# board.net
KiCad netlist of a schematic drawn in EAGLE
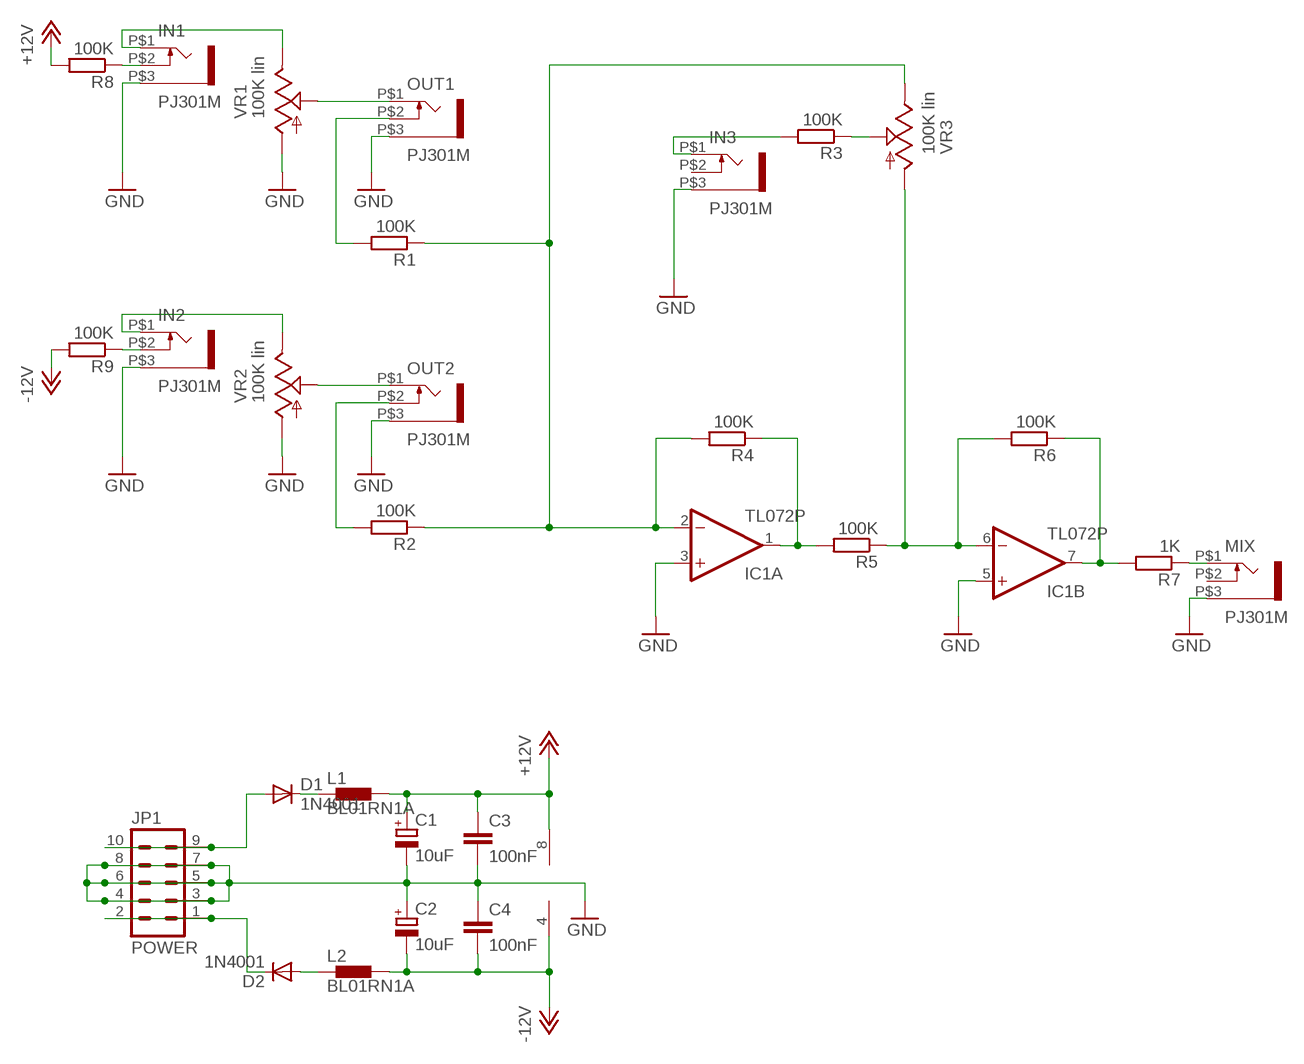
[diagram p0: schematic, sheet 1]

(export (version "E")
  (design (tool "Eeschema 10.0.6"))
  (components
    (comp (ref "C1")
      (value "10uF")
      (footprint "eagle-import:E2,5-6E")
      (fields (field (name "MF") "NICHICON") (field (name "MPN") "UVR2A100MED1TD"))
      (libsource (lib "eagle-import") (part "CPOL-EUE2,5-6E"))
    )
    (comp (ref "C2")
      (value "10uF")
      (footprint "eagle-import:E2,5-6E")
      (fields (field (name "MF") "NICHICON") (field (name "MPN") "UVR2A100MED1TD"))
      (libsource (lib "eagle-import") (part "CPOL-EUE2,5-6E"))
    )
    (comp (ref "C3")
      (value "100nF")
      (footprint "eagle-import:C025-024X044")
      (fields (field (name "MF") "MULTICOMP") (field (name "MPN") "MC0805Y104M500A2.54MM"))
      (libsource (lib "eagle-import") (part "C-EU025-024X044"))
    )
    (comp (ref "C4")
      (value "100nF")
      (footprint "eagle-import:C025-024X044")
      (fields (field (name "MF") "MULTICOMP") (field (name "MPN") "MC0805Y104M500A2.54MM"))
      (libsource (lib "eagle-import") (part "C-EU025-024X044"))
    )
    (comp (ref "D1")
      (value "1N4001")
      (footprint "eagle-import:DO41-10")
      (fields (field (name "MF") "VISHAY") (field (name "MPN") "1N4001-E3/54"))
      (libsource (lib "eagle-import") (part "1N4004"))
    )
    (comp (ref "D2")
      (value "1N4001")
      (footprint "eagle-import:DO41-10")
      (fields (field (name "MF") "VISHAY") (field (name "MPN") "1N4001-E3/54"))
      (libsource (lib "eagle-import") (part "1N4004"))
    )
    (comp (ref "IC1")
      (value "TL072P")
      (footprint "eagle-import:DIL08")
      (fields
        (field (name "MF") "TEXAS INSTRUMENTS")
        (field (name "MPN") "TL072IP")
        (field (name "OC_FARNELL") "3117794")
      )
      (libsource (lib "eagle-import") (part "TL072P"))
    )
    (comp (ref "IN1")
      (value "PJ301M")
      (footprint "eagle-import:WQP-PJ301M-12_JACK")
      (libsource (lib "eagle-import") (part "WQP-PJ301M-12_JACK"))
    )
    (comp (ref "IN2")
      (value "PJ301M")
      (footprint "eagle-import:WQP-PJ301M-12_JACK")
      (libsource (lib "eagle-import") (part "WQP-PJ301M-12_JACK"))
    )
    (comp (ref "IN3")
      (value "PJ301M")
      (footprint "eagle-import:WQP-PJ301M-12_JACK")
      (libsource (lib "eagle-import") (part "WQP-PJ301M-12_JACK"))
    )
    (comp (ref "JP1")
      (value "POWER")
      (footprint "eagle-import:EURO_PWR_HEADER_FAT")
      (fields (field (name "MF") "MULTICOMP PRO") (field (name "MPN") "2213S-10G"))
      (libsource (lib "eagle-import") (part "EURO_POWER_HEADERFAT_PADS"))
    )
    (comp (ref "L1")
      (value "BL01RN1A")
      (footprint "eagle-import:BL01RN1A")
      (fields (field (name "MF") "MURATA") (field (name "MPN") "BL01RN1A1D2B"))
      (libsource (lib "eagle-import") (part "BL01RN1A"))
    )
    (comp (ref "L2")
      (value "BL01RN1A")
      (footprint "eagle-import:BL01RN1A")
      (fields (field (name "MF") "MURATA") (field (name "MPN") "BL01RN1A1D2B"))
      (libsource (lib "eagle-import") (part "BL01RN1A"))
    )
    (comp (ref "MIX")
      (value "PJ301M")
      (footprint "eagle-import:WQP-PJ301M-12_JACK")
      (libsource (lib "eagle-import") (part "WQP-PJ301M-12_JACK"))
    )
    (comp (ref "OUT1")
      (value "PJ301M")
      (footprint "eagle-import:WQP-PJ301M-12_JACK")
      (libsource (lib "eagle-import") (part "WQP-PJ301M-12_JACK"))
    )
    (comp (ref "OUT2")
      (value "PJ301M")
      (footprint "eagle-import:WQP-PJ301M-12_JACK")
      (libsource (lib "eagle-import") (part "WQP-PJ301M-12_JACK"))
    )
    (comp (ref "R1")
      (value "100K")
      (footprint "eagle-import:0204_5")
      (fields (field (name "MF") "TE CONNECTIVITY") (field (name "MPN") "LR0204F100K"))
      (libsource (lib "eagle-import") (part "R-EU_0204/5"))
    )
    (comp (ref "R2")
      (value "100K")
      (footprint "eagle-import:0204_5")
      (fields (field (name "MF") "TE CONNECTIVITY") (field (name "MPN") "LR0204F100K"))
      (libsource (lib "eagle-import") (part "R-EU_0204/5"))
    )
    (comp (ref "R3")
      (value "100K")
      (footprint "eagle-import:0204_5")
      (fields (field (name "MF") "TE CONNECTIVITY") (field (name "MPN") "LR0204F100K"))
      (libsource (lib "eagle-import") (part "R-EU_0204/5"))
    )
    (comp (ref "R4")
      (value "100K")
      (footprint "eagle-import:0204_5")
      (fields (field (name "MF") "TE CONNECTIVITY") (field (name "MPN") "LR0204F100K"))
      (libsource (lib "eagle-import") (part "R-EU_0204/5"))
    )
    (comp (ref "R5")
      (value "100K")
      (footprint "eagle-import:0204_5")
      (fields (field (name "MF") "TE CONNECTIVITY") (field (name "MPN") "LR0204F100K"))
      (libsource (lib "eagle-import") (part "R-EU_0204/5"))
    )
    (comp (ref "R6")
      (value "100K")
      (footprint "eagle-import:0204_5")
      (fields (field (name "MF") "TE CONNECTIVITY") (field (name "MPN") "LR0204F100K"))
      (libsource (lib "eagle-import") (part "R-EU_0204/5"))
    )
    (comp (ref "R7")
      (value "1K")
      (footprint "eagle-import:0204_5")
      (fields (field (name "MF") "TE CONNECTIVITY") (field (name "MPN") "LR0204F1K0"))
      (libsource (lib "eagle-import") (part "R-EU_0204/5"))
    )
    (comp (ref "R8")
      (value "100K")
      (footprint "eagle-import:0204_5")
      (fields (field (name "MF") "TE CONNECTIVITY") (field (name "MPN") "LR0204F100K"))
      (libsource (lib "eagle-import") (part "R-EU_0204/5"))
    )
    (comp (ref "R9")
      (value "100K")
      (footprint "eagle-import:0204_5")
      (fields (field (name "MF") "TE CONNECTIVITY") (field (name "MPN") "LR0204F100K"))
      (libsource (lib "eagle-import") (part "R-EU_0204/5"))
    )
    (comp (ref "VR1")
      (value "100K lin")
      (footprint "eagle-import:9MM_SNAP-IN_POT")
      (libsource (lib "eagle-import") (part "9MM_SNAP-IN_POT_"))
    )
    (comp (ref "VR2")
      (value "100K lin")
      (footprint "eagle-import:9MM_SNAP-IN_POT")
      (libsource (lib "eagle-import") (part "9MM_SNAP-IN_POT_"))
    )
    (comp (ref "VR3")
      (value "100K lin")
      (footprint "eagle-import:9MM_SNAP-IN_POT")
      (libsource (lib "eagle-import") (part "9MM_SNAP-IN_POT_"))
    )
  )
  (nets
    (net (code "1") (name "+12V") (class "Default")
      (node (ref "C1") (pin "+") (pinfunction "+_+") (pintype "passive"))
      (node (ref "C3") (pin "1") (pinfunction "1_1") (pintype "passive"))
      (node (ref "IC1") (pin "8") (pinfunction "V+_8") (pintype "power_in"))
      (node (ref "L1") (pin "2") (pinfunction "2_2") (pintype "passive"))
      (node (ref "R8") (pin "2") (pinfunction "2_2") (pintype "passive"))
    )
    (net (code "2") (name "-12V") (class "Default")
      (node (ref "C2") (pin "-") (pinfunction "-_-") (pintype "passive"))
      (node (ref "C4") (pin "2") (pinfunction "2_2") (pintype "passive"))
      (node (ref "IC1") (pin "4") (pinfunction "V-_4") (pintype "power_in"))
      (node (ref "L2") (pin "2") (pinfunction "2_2") (pintype "passive"))
      (node (ref "R9") (pin "2") (pinfunction "2_2") (pintype "passive"))
    )
    (net (code "3") (name "GND") (class "Default")
      (node (ref "C1") (pin "-") (pinfunction "-_-") (pintype "passive"))
      (node (ref "C2") (pin "+") (pinfunction "+_+") (pintype "passive"))
      (node (ref "C3") (pin "2") (pinfunction "2_2") (pintype "passive"))
      (node (ref "C4") (pin "1") (pinfunction "1_1") (pintype "passive"))
      (node (ref "IC1") (pin "3") (pinfunction "+IN_3") (pintype "input"))
      (node (ref "IC1") (pin "5") (pinfunction "+IN_5") (pintype "input"))
      (node (ref "IN1") (pin "P$3") (pinfunction "1_P$3") (pintype "passive"))
      (node (ref "IN2") (pin "P$3") (pinfunction "1_P$3") (pintype "passive"))
      (node (ref "IN3") (pin "P$3") (pinfunction "1_P$3") (pintype "passive"))
      (node (ref "JP1") (pin "3") (pinfunction "3_3") (pintype "passive"))
      (node (ref "JP1") (pin "4") (pinfunction "4_4") (pintype "passive"))
      (node (ref "JP1") (pin "5") (pinfunction "5_5") (pintype "passive"))
      (node (ref "JP1") (pin "6") (pinfunction "6_6") (pintype "passive"))
      (node (ref "JP1") (pin "7") (pinfunction "7_7") (pintype "passive"))
      (node (ref "JP1") (pin "8") (pinfunction "8_8") (pintype "passive"))
      (node (ref "MIX") (pin "P$3") (pinfunction "1_P$3") (pintype "passive"))
      (node (ref "OUT1") (pin "P$3") (pinfunction "1_P$3") (pintype "passive"))
      (node (ref "OUT2") (pin "P$3") (pinfunction "1_P$3") (pintype "passive"))
      (node (ref "VR1") (pin "1") (pinfunction "A_1") (pintype "passive"))
      (node (ref "VR2") (pin "1") (pinfunction "A_1") (pintype "passive"))
    )
    (net (code "4") (name "Net-(D1-PadA)") (class "Default")
      (node (ref "D1") (pin "A") (pinfunction "A_A") (pintype "passive"))
      (node (ref "JP1") (pin "10") (pinfunction "10_10") (pintype "passive"))
      (node (ref "JP1") (pin "9") (pinfunction "9_9") (pintype "passive"))
    )
    (net (code "5") (name "Net-(D1-PadC)") (class "Default")
      (node (ref "D1") (pin "C") (pinfunction "C_C") (pintype "passive"))
      (node (ref "L1") (pin "1") (pinfunction "1_1") (pintype "passive"))
    )
    (net (code "6") (name "Net-(D2-PadA)") (class "Default")
      (node (ref "D2") (pin "A") (pinfunction "A_A") (pintype "passive"))
      (node (ref "L2") (pin "1") (pinfunction "1_1") (pintype "passive"))
    )
    (net (code "7") (name "Net-(D2-PadC)") (class "Default")
      (node (ref "D2") (pin "C") (pinfunction "C_C") (pintype "passive"))
      (node (ref "JP1") (pin "1") (pinfunction "1_1") (pintype "passive"))
      (node (ref "JP1") (pin "2") (pinfunction "2_2") (pintype "passive"))
    )
    (net (code "8") (name "Net-(IC1A--IN)") (class "Default")
      (node (ref "IC1") (pin "2") (pinfunction "-IN_2") (pintype "input"))
      (node (ref "R1") (pin "1") (pinfunction "1_1") (pintype "passive"))
      (node (ref "R2") (pin "1") (pinfunction "1_1") (pintype "passive"))
      (node (ref "R4") (pin "2") (pinfunction "2_2") (pintype "passive"))
      (node (ref "VR3") (pin "3") (pinfunction "E_3") (pintype "passive"))
    )
    (net (code "9") (name "Net-(IC1A-OUT)") (class "Default")
      (node (ref "IC1") (pin "1") (pinfunction "OUT_1") (pintype "output"))
      (node (ref "R4") (pin "1") (pinfunction "1_1") (pintype "passive"))
      (node (ref "R5") (pin "2") (pinfunction "2_2") (pintype "passive"))
    )
    (net (code "10") (name "Net-(IC1B--IN)") (class "Default")
      (node (ref "IC1") (pin "6") (pinfunction "-IN_6") (pintype "input"))
      (node (ref "R5") (pin "1") (pinfunction "1_1") (pintype "passive"))
      (node (ref "R6") (pin "2") (pinfunction "2_2") (pintype "passive"))
      (node (ref "VR3") (pin "1") (pinfunction "A_1") (pintype "passive"))
    )
    (net (code "11") (name "Net-(IC1B-OUT)") (class "Default")
      (node (ref "IC1") (pin "7") (pinfunction "OUT_7") (pintype "output"))
      (node (ref "R6") (pin "1") (pinfunction "1_1") (pintype "passive"))
      (node (ref "R7") (pin "2") (pinfunction "2_2") (pintype "passive"))
    )
    (net (code "12") (name "Net-(IN1-2)") (class "Default")
      (node (ref "IN1") (pin "P$1") (pinfunction "2_P$1") (pintype "passive"))
      (node (ref "VR1") (pin "3") (pinfunction "E_3") (pintype "passive"))
    )
    (net (code "13") (name "Net-(IN1-3)") (class "Default")
      (node (ref "IN1") (pin "P$2") (pinfunction "3_P$2") (pintype "passive"))
      (node (ref "R8") (pin "1") (pinfunction "1_1") (pintype "passive"))
    )
    (net (code "14") (name "Net-(IN2-2)") (class "Default")
      (node (ref "IN2") (pin "P$1") (pinfunction "2_P$1") (pintype "passive"))
      (node (ref "VR2") (pin "3") (pinfunction "E_3") (pintype "passive"))
    )
    (net (code "15") (name "Net-(IN2-3)") (class "Default")
      (node (ref "IN2") (pin "P$2") (pinfunction "3_P$2") (pintype "passive"))
      (node (ref "R9") (pin "1") (pinfunction "1_1") (pintype "passive"))
    )
    (net (code "16") (name "Net-(IN3-2)") (class "Default")
      (node (ref "IN3") (pin "P$1") (pinfunction "2_P$1") (pintype "passive"))
      (node (ref "R3") (pin "2") (pinfunction "2_2") (pintype "passive"))
    )
    (net (code "17") (name "Net-(MIX-2)") (class "Default")
      (node (ref "MIX") (pin "P$1") (pinfunction "2_P$1") (pintype "passive"))
      (node (ref "R7") (pin "1") (pinfunction "1_1") (pintype "passive"))
    )
    (net (code "18") (name "Net-(OUT1-2)") (class "Default")
      (node (ref "OUT1") (pin "P$1") (pinfunction "2_P$1") (pintype "passive"))
      (node (ref "VR1") (pin "2") (pinfunction "S_2") (pintype "passive"))
    )
    (net (code "19") (name "Net-(OUT1-3)") (class "Default")
      (node (ref "OUT1") (pin "P$2") (pinfunction "3_P$2") (pintype "passive"))
      (node (ref "R1") (pin "2") (pinfunction "2_2") (pintype "passive"))
    )
    (net (code "20") (name "Net-(OUT2-2)") (class "Default")
      (node (ref "OUT2") (pin "P$1") (pinfunction "2_P$1") (pintype "passive"))
      (node (ref "VR2") (pin "2") (pinfunction "S_2") (pintype "passive"))
    )
    (net (code "21") (name "Net-(OUT2-3)") (class "Default")
      (node (ref "OUT2") (pin "P$2") (pinfunction "3_P$2") (pintype "passive"))
      (node (ref "R2") (pin "2") (pinfunction "2_2") (pintype "passive"))
    )
    (net (code "22") (name "Net-(VR3-S)") (class "Default")
      (node (ref "R3") (pin "1") (pinfunction "1_1") (pintype "passive"))
      (node (ref "VR3") (pin "2") (pinfunction "S_2") (pintype "passive"))
    )
    (net (code "23") (name "unconnected-(IN3-3-PadP$2)") (class "Default")
      (node (ref "IN3") (pin "P$2") (pinfunction "3_P$2") (pintype "passive"))
    )
    (net (code "24") (name "unconnected-(MIX-3-PadP$2)") (class "Default")
      (node (ref "MIX") (pin "P$2") (pinfunction "3_P$2") (pintype "passive"))
    )
  )
)
